# HandheldCon.net
KiCad netlist of a schematic drawn in Altium Designer
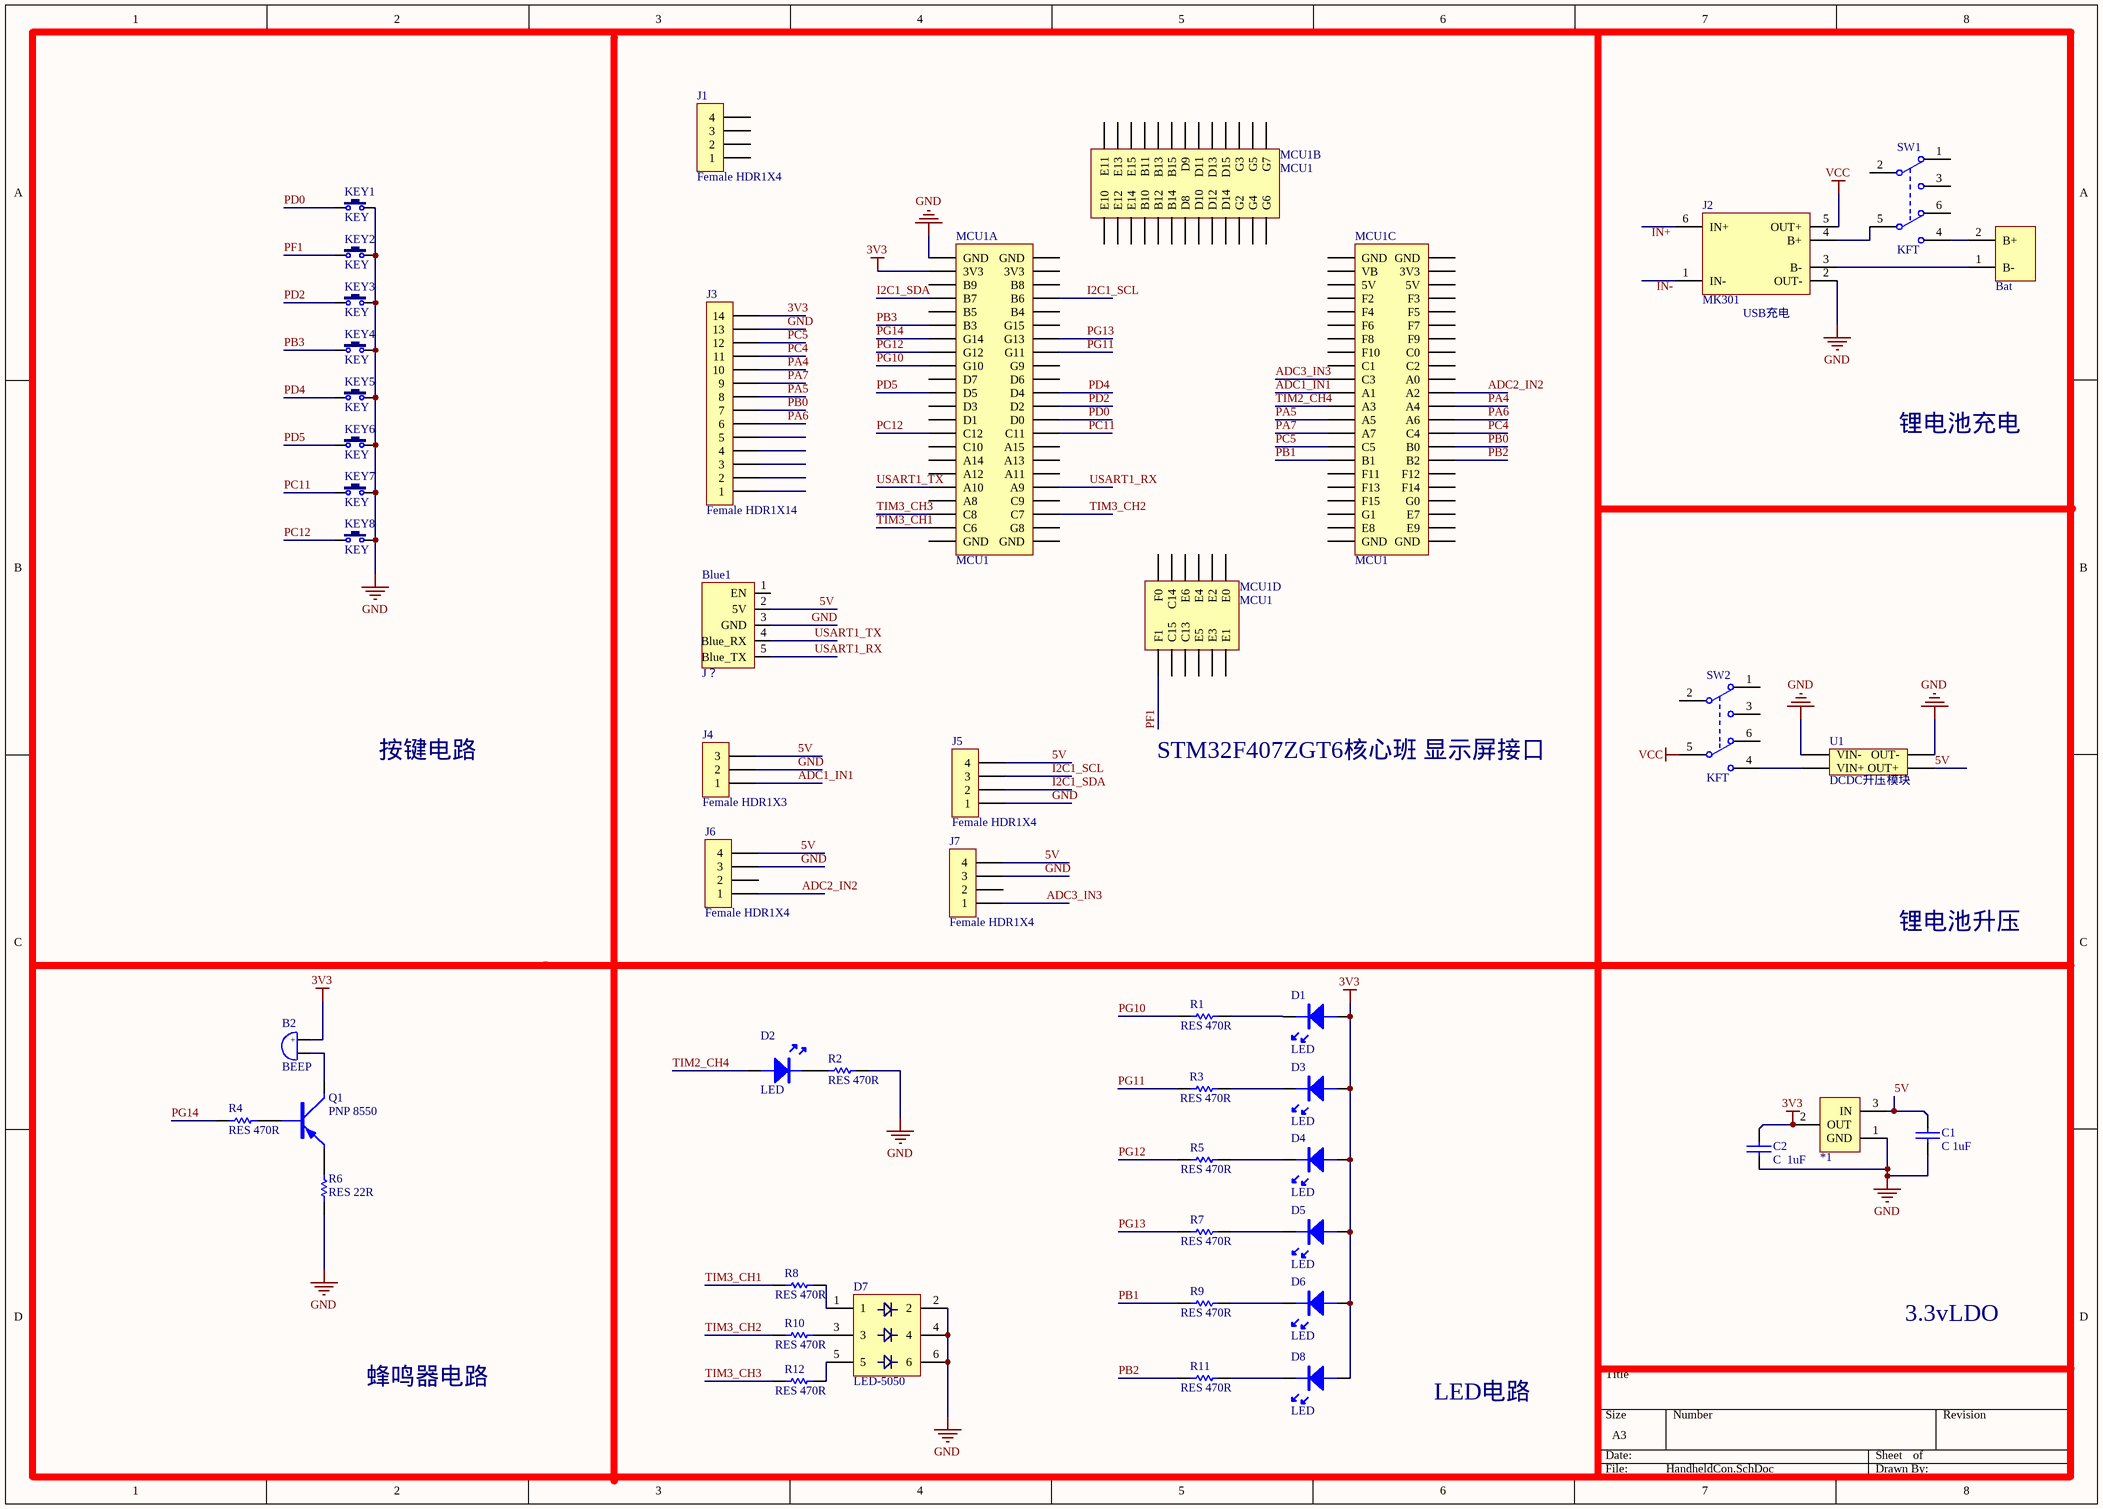
[diagram p0: HandheldCon.SchDoc]

(export (version "E")
  (design (tool "Eeschema 10.0.6"))
  (components
    (comp (ref "*1") (value "3Vout") (footprint "ASM1117_3.3V") (libsource (lib "Schlib1") (part "LM1117")))
    (comp (ref "B1") (value "Bat") (footprint "XH2.54-LI-2P") (libsource (lib "Schlib1") (part "Bettry")))
    (comp (ref "B2")
      (value "BEEP")
      (footprint "BEEP 5x9x5.5")
      (description "蜂鸣器")
      (libsource (lib "蜂鸣器") (part "BEEP"))
    )
    (comp (ref "Blue1")
      (value "J？")
      (footprint "HDR2.54-M-LI-5P")
      (libsource (lib "Schlib_autocar") (part "BlueTooth_net"))
    )
    (comp (ref "C1")
      (value "C 1uF")
      (footprint "1206C")
      (description "Capacitor")
      (libsource (lib "Schlib1") (part "CAP1206"))
    )
    (comp (ref "C2")
      (value "C  1uF")
      (footprint "1206C")
      (description "Capacitor")
      (libsource (lib "Schlib1") (part "CAP1206"))
    )
    (comp (ref "D1") (value "LED") (footprint "LED-0805R") (libsource (lib "LED") (part "LED")))
    (comp (ref "D2") (value "LED") (footprint "LED-0805R") (libsource (lib "LED") (part "LED")))
    (comp (ref "D3") (value "LED") (footprint "LED-0805Y") (libsource (lib "LED") (part "LED")))
    (comp (ref "D4") (value "LED") (footprint "LED-0805B") (libsource (lib "LED") (part "LED")))
    (comp (ref "D5") (value "LED") (footprint "LED-0805G") (libsource (lib "LED") (part "LED")))
    (comp (ref "D6") (value "LED") (footprint "LED-0805G") (libsource (lib "LED") (part "LED")))
    (comp (ref "D7") (value "LED-5050") (footprint "LED-5050W") (libsource (lib "LED") (part "LED-5050")))
    (comp (ref "D8") (value "LED") (footprint "LED-0805G") (libsource (lib "LED") (part "LED")))
    (comp (ref "J1")
      (value "Female HDR1X4")
      (footprint "Fe-HDR1X4/2.54-S")
      (libsource (lib "排母") (part "Female HDR1X4"))
    )
    (comp (ref "J2") (value "MK301") (footprint "TP4056") (libsource (lib "Schlib1") (part "MK301")))
    (comp (ref "J3")
      (value "Female HDR1X14")
      (footprint "Fe-HDR1X14/2.54-S")
      (libsource (lib "排母") (part "Female HDR1X14"))
    )
    (comp (ref "J4")
      (value "Female HDR1X3")
      (footprint "Fe-HDR1X3/2.54-S")
      (libsource (lib "排母") (part "Female HDR1X3"))
    )
    (comp (ref "J5")
      (value "Female HDR1X4")
      (footprint "Fe-HDR1X4/2.54-S")
      (libsource (lib "排母") (part "Female HDR1X4"))
    )
    (comp (ref "J6")
      (value "Female HDR1X4")
      (footprint "Fe-HDR1X4/2.54-S")
      (libsource (lib "排母") (part "Female HDR1X4"))
    )
    (comp (ref "J7")
      (value "Female HDR1X4")
      (footprint "Fe-HDR1X4/2.54-S")
      (libsource (lib "排母") (part "Female HDR1X4"))
    )
    (comp (ref "KEY1")
      (value "KEY")
      (footprint "TSW SMD-6*6*8")
      (description "Tact Switch")
      (libsource (lib "集成库文件") (part "TSW_6X6-SMT"))
    )
    (comp (ref "KEY2")
      (value "KEY")
      (footprint "TSW SMD-6*6*8")
      (description "Tact Switch")
      (libsource (lib "集成库文件") (part "TSW_6X6-SMT"))
    )
    (comp (ref "KEY3")
      (value "KEY")
      (footprint "TSW SMD-6*6*8")
      (description "Tact Switch")
      (libsource (lib "集成库文件") (part "TSW_6X6-SMT"))
    )
    (comp (ref "KEY4")
      (value "KEY")
      (footprint "TSW SMD-6*6*8")
      (description "Tact Switch")
      (libsource (lib "集成库文件") (part "TSW_6X6-SMT"))
    )
    (comp (ref "KEY5")
      (value "KEY")
      (footprint "TSW SMD-6*6*8")
      (description "Tact Switch")
      (libsource (lib "集成库文件") (part "TSW_6X6-SMT"))
    )
    (comp (ref "KEY6")
      (value "KEY")
      (footprint "TSW SMD-6*6*8")
      (description "Tact Switch")
      (libsource (lib "集成库文件") (part "TSW_6X6-SMT"))
    )
    (comp (ref "KEY7")
      (value "KEY")
      (footprint "TSW SMD-6*6*8")
      (description "Tact Switch")
      (libsource (lib "集成库文件") (part "TSW_6X6-SMT"))
    )
    (comp (ref "KEY8")
      (value "KEY")
      (footprint "TSW SMD-6*6*8")
      (description "Tact Switch")
      (libsource (lib "集成库文件") (part "TSW_6X6-SMT"))
    )
    (comp (ref "MCU1") (value "MCU1") (footprint "核心板底座") (libsource (lib "Schlib_autocar") (part "核心板插座")))
    (comp (ref "Q1")
      (value "PNP 8550")
      (footprint "SOT-23")
      (description "PNP三极管")
      (libsource (lib "三极管") (part "PNP"))
    )
    (comp (ref "R1") (value "RES 470R") (footprint "0805R") (libsource (lib "电阻") (part "RES")))
    (comp (ref "R2") (value "RES 470R") (footprint "0805R") (libsource (lib "电阻") (part "RES")))
    (comp (ref "R3") (value "RES 470R") (footprint "0805R") (libsource (lib "电阻") (part "RES")))
    (comp (ref "R4") (value "RES 470R") (footprint "0805R") (libsource (lib "电阻") (part "RES")))
    (comp (ref "R5") (value "RES 470R") (footprint "0805R") (libsource (lib "电阻") (part "RES")))
    (comp (ref "R6") (value "RES 22R") (footprint "0805R") (libsource (lib "电阻") (part "RES")))
    (comp (ref "R7") (value "RES 470R") (footprint "0805R") (libsource (lib "电阻") (part "RES")))
    (comp (ref "R8") (value "RES 470R") (footprint "0805R") (libsource (lib "电阻") (part "RES")))
    (comp (ref "R9") (value "RES 470R") (footprint "0805R") (libsource (lib "电阻") (part "RES")))
    (comp (ref "R10") (value "RES 470R") (footprint "0805R") (libsource (lib "电阻") (part "RES")))
    (comp (ref "R11") (value "RES 470R") (footprint "0805R") (libsource (lib "电阻") (part "RES")))
    (comp (ref "R12") (value "RES 470R") (footprint "0805R") (libsource (lib "电阻") (part "RES")))
    (comp (ref "SW1")
      (value "KFT")
      (footprint "KFT DIP-7X7")
      (description "Self-locking Switch")
      (libsource (lib "Schlib1") (part "KFT_7X7-DIP"))
    )
    (comp (ref "SW2")
      (value "KFT")
      (footprint "KFT DIP-7X7")
      (description "Self-locking Switch")
      (libsource (lib "Schlib1") (part "KFT_7X7-DIP"))
    )
    (comp (ref "U1") (value "DCDC升压模块") (footprint "DCDC升压5V") (libsource (lib "Schlib1") (part "DCDC升压模块")))
  )
  (nets
    (net (code "1") (name "/5V") (class "Default")
      (node (ref "*1") (pin "3") (pinfunction "IN_3") (pintype "power_in"))
      (node (ref "Blue1") (pin "2") (pinfunction "5V_2") (pintype "power_in"))
      (node (ref "C1") (pin "1") (pinfunction "1_1") (pintype "passive"))
      (node (ref "J4") (pin "3") (pinfunction "3_3") (pintype "passive"))
      (node (ref "J5") (pin "4") (pinfunction "4_4") (pintype "passive"))
      (node (ref "J6") (pin "4") (pinfunction "4_4") (pintype "passive"))
      (node (ref "J7") (pin "4") (pinfunction "4_4") (pintype "passive"))
      (node (ref "U1") (pin "1") (pinfunction "OUT+_1") (pintype "passive"))
    )
    (net (code "2") (name "/ADC1_IN1") (class "Default")
      (node (ref "J4") (pin "1") (pinfunction "1_1") (pintype "passive"))
      (node (ref "MCU1") (pin "94") (pinfunction "A1_94") (pintype "passive"))
    )
    (net (code "3") (name "/ADC2_IN2") (class "Default")
      (node (ref "J6") (pin "1") (pinfunction "1_1") (pintype "passive"))
      (node (ref "MCU1") (pin "93") (pinfunction "A2_93") (pintype "passive"))
    )
    (net (code "4") (name "/ADC3_IN3") (class "Default")
      (node (ref "J7") (pin "1") (pinfunction "1_1") (pintype "passive"))
      (node (ref "MCU1") (pin "96") (pinfunction "C3_96") (pintype "passive"))
    )
    (net (code "5") (name "/I2C1_SCL") (class "Default")
      (node (ref "J5") (pin "3") (pinfunction "3_3") (pintype "passive"))
      (node (ref "MCU1") (pin "8") (pinfunction "B6_8") (pintype "passive"))
    )
    (net (code "6") (name "/I2C1_SDA") (class "Default")
      (node (ref "J5") (pin "2") (pinfunction "2_2") (pintype "passive"))
      (node (ref "MCU1") (pin "7") (pinfunction "B7_7") (pintype "passive"))
    )
    (net (code "9") (name "/PA4") (class "Default")
      (node (ref "J3") (pin "10") (pinfunction "10_10") (pintype "passive"))
      (node (ref "MCU1") (pin "91") (pinfunction "A4_91") (pintype "passive"))
    )
    (net (code "10") (name "/PA5") (class "Default")
      (node (ref "J3") (pin "8") (pinfunction "8_8") (pintype "passive"))
      (node (ref "MCU1") (pin "90") (pinfunction "A5_90") (pintype "passive"))
    )
    (net (code "11") (name "/PA6") (class "Default")
      (node (ref "J3") (pin "6") (pinfunction "6_6") (pintype "passive"))
      (node (ref "MCU1") (pin "89") (pinfunction "A6_89") (pintype "passive"))
    )
    (net (code "12") (name "/PA7") (class "Default")
      (node (ref "J3") (pin "9") (pinfunction "9_9") (pintype "passive"))
      (node (ref "MCU1") (pin "88") (pinfunction "A7_88") (pintype "passive"))
    )
    (net (code "13") (name "/PB0") (class "Default")
      (node (ref "J3") (pin "7") (pinfunction "7_7") (pintype "passive"))
      (node (ref "MCU1") (pin "85") (pinfunction "B0_85") (pintype "passive"))
    )
    (net (code "14") (name "/PB1") (class "Default")
      (node (ref "MCU1") (pin "84") (pinfunction "B1_84") (pintype "passive"))
      (node (ref "R9") (pin "1") (pinfunction "1_1") (pintype "passive"))
    )
    (net (code "15") (name "/PB2") (class "Default")
      (node (ref "MCU1") (pin "83") (pinfunction "B2_83") (pintype "passive"))
      (node (ref "R11") (pin "1") (pinfunction "1_1") (pintype "passive"))
    )
    (net (code "16") (name "/PB3") (class "Default")
      (node (ref "KEY4") (pin "1") (pinfunction "1_1") (pintype "passive"))
      (node (ref "MCU1") (pin "11") (pinfunction "B3_11") (pintype "passive"))
    )
    (net (code "17") (name "/PC4") (class "Default")
      (node (ref "J3") (pin "11") (pinfunction "11_11") (pintype "passive"))
      (node (ref "MCU1") (pin "87") (pinfunction "C4_87") (pintype "passive"))
    )
    (net (code "18") (name "/PC5") (class "Default")
      (node (ref "J3") (pin "12") (pinfunction "12_12") (pintype "passive"))
      (node (ref "MCU1") (pin "86") (pinfunction "C5_86") (pintype "passive"))
    )
    (net (code "19") (name "/PC11") (class "Default")
      (node (ref "KEY7") (pin "1") (pinfunction "1_1") (pintype "passive"))
      (node (ref "MCU1") (pin "28") (pinfunction "C11_28") (pintype "passive"))
    )
    (net (code "20") (name "/PC12") (class "Default")
      (node (ref "KEY8") (pin "1") (pinfunction "1_1") (pintype "passive"))
      (node (ref "MCU1") (pin "27") (pinfunction "C12_27") (pintype "passive"))
    )
    (net (code "21") (name "/PD0") (class "Default")
      (node (ref "KEY1") (pin "1") (pinfunction "1_1") (pintype "passive"))
      (node (ref "MCU1") (pin "26") (pinfunction "D0_26") (pintype "passive"))
    )
    (net (code "22") (name "/PD2") (class "Default")
      (node (ref "KEY3") (pin "1") (pinfunction "1_1") (pintype "passive"))
      (node (ref "MCU1") (pin "24") (pinfunction "D2_24") (pintype "passive"))
    )
    (net (code "23") (name "/PD4") (class "Default")
      (node (ref "KEY5") (pin "1") (pinfunction "1_1") (pintype "passive"))
      (node (ref "MCU1") (pin "22") (pinfunction "D4_22") (pintype "passive"))
    )
    (net (code "24") (name "/PD5") (class "Default")
      (node (ref "KEY6") (pin "1") (pinfunction "1_1") (pintype "passive"))
      (node (ref "MCU1") (pin "21") (pinfunction "D5_21") (pintype "passive"))
    )
    (net (code "25") (name "/PF1") (class "Default")
      (node (ref "KEY2") (pin "1") (pinfunction "1_1") (pintype "passive"))
      (node (ref "MCU1") (pin "115") (pinfunction "F1_115") (pintype "passive"))
    )
    (net (code "26") (name "/PG10") (class "Default")
      (node (ref "MCU1") (pin "17") (pinfunction "G10_17") (pintype "passive"))
      (node (ref "R1") (pin "1") (pinfunction "1_1") (pintype "passive"))
    )
    (net (code "27") (name "/PG11") (class "Default")
      (node (ref "MCU1") (pin "16") (pinfunction "G11_16") (pintype "passive"))
      (node (ref "R3") (pin "1") (pinfunction "1_1") (pintype "passive"))
    )
    (net (code "28") (name "/PG12") (class "Default")
      (node (ref "MCU1") (pin "15") (pinfunction "G12_15") (pintype "passive"))
      (node (ref "R5") (pin "1") (pinfunction "1_1") (pintype "passive"))
    )
    (net (code "29") (name "/PG13") (class "Default")
      (node (ref "MCU1") (pin "14") (pinfunction "G13_14") (pintype "passive"))
      (node (ref "R7") (pin "1") (pinfunction "1_1") (pintype "passive"))
    )
    (net (code "30") (name "/PG14") (class "Default")
      (node (ref "MCU1") (pin "13") (pinfunction "G14_13") (pintype "passive"))
      (node (ref "R4") (pin "2") (pinfunction "2_2") (pintype "passive"))
    )
    (net (code "31") (name "/TIM2_CH4") (class "Default")
      (node (ref "D2") (pin "A") (pinfunction "A_A") (pintype "passive"))
      (node (ref "MCU1") (pin "92") (pinfunction "A3_92") (pintype "passive"))
    )
    (net (code "32") (name "/TIM3_CH1") (class "Default")
      (node (ref "MCU1") (pin "41") (pinfunction "C6_41") (pintype "passive"))
      (node (ref "R8") (pin "1") (pinfunction "1_1") (pintype "passive"))
    )
    (net (code "33") (name "/TIM3_CH2") (class "Default")
      (node (ref "MCU1") (pin "40") (pinfunction "C7_40") (pintype "passive"))
      (node (ref "R10") (pin "1") (pinfunction "1_1") (pintype "passive"))
    )
    (net (code "34") (name "/TIM3_CH3") (class "Default")
      (node (ref "MCU1") (pin "39") (pinfunction "C8_39") (pintype "passive"))
      (node (ref "R12") (pin "1") (pinfunction "1_1") (pintype "passive"))
    )
    (net (code "35") (name "/USART1_RX") (class "Default")
      (node (ref "Blue1") (pin "5") (pinfunction "Blue_TX_5") (pintype "passive"))
      (node (ref "MCU1") (pin "36") (pinfunction "A9_36") (pintype "passive"))
    )
    (net (code "36") (name "/USART1_TX") (class "Default")
      (node (ref "Blue1") (pin "4") (pinfunction "Blue_RX_4") (pintype "passive"))
      (node (ref "MCU1") (pin "35") (pinfunction "A10_35") (pintype "passive"))
    )
    (net (code "37") (name "3V3") (class "Default")
      (node (ref "*1") (pin "2") (pinfunction "OUT_2") (pintype "power_in"))
      (node (ref "B2") (pin "1") (pinfunction "1_1") (pintype "passive"))
      (node (ref "C2") (pin "1") (pinfunction "1_1") (pintype "passive"))
      (node (ref "D1") (pin "A") (pinfunction "A_A") (pintype "passive"))
      (node (ref "D3") (pin "A") (pinfunction "A_A") (pintype "passive"))
      (node (ref "D4") (pin "A") (pinfunction "A_A") (pintype "passive"))
      (node (ref "D5") (pin "A") (pinfunction "A_A") (pintype "passive"))
      (node (ref "D6") (pin "A") (pinfunction "A_A") (pintype "passive"))
      (node (ref "D8") (pin "A") (pinfunction "A_A") (pintype "passive"))
      (node (ref "J3") (pin "14") (pinfunction "14_14") (pintype "passive"))
      (node (ref "MCU1") (pin "3") (pinfunction "3V3_3") (pintype "passive"))
    )
    (net (code "38") (name "GND") (class "Default")
      (node (ref "*1") (pin "1") (pinfunction "GND_1") (pintype "power_in"))
      (node (ref "Blue1") (pin "3") (pinfunction "GND_3") (pintype "power_in"))
      (node (ref "C1") (pin "2") (pinfunction "2_2") (pintype "passive"))
      (node (ref "C2") (pin "2") (pinfunction "2_2") (pintype "passive"))
      (node (ref "D7") (pin "2") (pinfunction "2_2") (pintype "passive"))
      (node (ref "D7") (pin "4") (pinfunction "4_4") (pintype "passive"))
      (node (ref "D7") (pin "6") (pinfunction "6_6") (pintype "passive"))
      (node (ref "J2") (pin "2") (pinfunction "OUT-_2") (pintype "power_in"))
      (node (ref "J3") (pin "13") (pinfunction "13_13") (pintype "passive"))
      (node (ref "J4") (pin "2") (pinfunction "2_2") (pintype "passive"))
      (node (ref "J5") (pin "1") (pinfunction "1_1") (pintype "passive"))
      (node (ref "J6") (pin "3") (pinfunction "3_3") (pintype "passive"))
      (node (ref "J7") (pin "3") (pinfunction "3_3") (pintype "passive"))
      (node (ref "KEY1") (pin "2") (pinfunction "2_2") (pintype "passive"))
      (node (ref "KEY2") (pin "2") (pinfunction "2_2") (pintype "passive"))
      (node (ref "KEY3") (pin "2") (pinfunction "2_2") (pintype "passive"))
      (node (ref "KEY4") (pin "2") (pinfunction "2_2") (pintype "passive"))
      (node (ref "KEY5") (pin "2") (pinfunction "2_2") (pintype "passive"))
      (node (ref "KEY6") (pin "2") (pinfunction "2_2") (pintype "passive"))
      (node (ref "KEY7") (pin "2") (pinfunction "2_2") (pintype "passive"))
      (node (ref "KEY8") (pin "2") (pinfunction "2_2") (pintype "passive"))
      (node (ref "MCU1") (pin "1") (pinfunction "GND_1") (pintype "power_in"))
      (node (ref "R2") (pin "1") (pinfunction "1_1") (pintype "passive"))
      (node (ref "R6") (pin "2") (pinfunction "2_2") (pintype "passive"))
      (node (ref "U1") (pin "2") (pinfunction "OUT-_2") (pintype "passive"))
      (node (ref "U1") (pin "3") (pinfunction "VIN-_3") (pintype "passive"))
    )
    (net (code "39") (name "Net-(B1-B+)") (class "Default")
      (node (ref "B1") (pin "2") (pinfunction "B+_2") (pintype "power_in"))
      (node (ref "SW1") (pin "4") (pinfunction "NO2_4") (pintype "passive"))
    )
    (net (code "40") (name "Net-(B1-B-)") (class "Default")
      (node (ref "B1") (pin "1") (pinfunction "B-_1") (pintype "power_in"))
      (node (ref "J2") (pin "3") (pinfunction "B-_3") (pintype "power_in"))
    )
    (net (code "41") (name "Net-(B2-Pad2)") (class "Default")
      (node (ref "B2") (pin "2") (pinfunction "2_2") (pintype "passive"))
      (node (ref "Q1") (pin "C") (pinfunction "C_C") (pintype "passive"))
    )
    (net (code "42") (name "Net-(D1-PadK)") (class "Default")
      (node (ref "D1") (pin "K") (pinfunction "K_K") (pintype "passive"))
      (node (ref "R1") (pin "2") (pinfunction "2_2") (pintype "passive"))
    )
    (net (code "43") (name "Net-(D2-PadK)") (class "Default")
      (node (ref "D2") (pin "K") (pinfunction "K_K") (pintype "passive"))
      (node (ref "R2") (pin "2") (pinfunction "2_2") (pintype "passive"))
    )
    (net (code "44") (name "Net-(D3-PadK)") (class "Default")
      (node (ref "D3") (pin "K") (pinfunction "K_K") (pintype "passive"))
      (node (ref "R3") (pin "2") (pinfunction "2_2") (pintype "passive"))
    )
    (net (code "45") (name "Net-(D4-PadK)") (class "Default")
      (node (ref "D4") (pin "K") (pinfunction "K_K") (pintype "passive"))
      (node (ref "R5") (pin "2") (pinfunction "2_2") (pintype "passive"))
    )
    (net (code "46") (name "Net-(D5-PadK)") (class "Default")
      (node (ref "D5") (pin "K") (pinfunction "K_K") (pintype "passive"))
      (node (ref "R7") (pin "2") (pinfunction "2_2") (pintype "passive"))
    )
    (net (code "47") (name "Net-(D6-PadK)") (class "Default")
      (node (ref "D6") (pin "K") (pinfunction "K_K") (pintype "passive"))
      (node (ref "R9") (pin "2") (pinfunction "2_2") (pintype "passive"))
    )
    (net (code "48") (name "Net-(D7-Pad1)") (class "Default")
      (node (ref "D7") (pin "1") (pinfunction "1_1") (pintype "passive"))
      (node (ref "R8") (pin "2") (pinfunction "2_2") (pintype "passive"))
    )
    (net (code "49") (name "Net-(D7-Pad3)") (class "Default")
      (node (ref "D7") (pin "3") (pinfunction "3_3") (pintype "passive"))
      (node (ref "R10") (pin "2") (pinfunction "2_2") (pintype "passive"))
    )
    (net (code "50") (name "Net-(D7-Pad5)") (class "Default")
      (node (ref "D7") (pin "5") (pinfunction "5_5") (pintype "passive"))
      (node (ref "R12") (pin "2") (pinfunction "2_2") (pintype "passive"))
    )
    (net (code "51") (name "Net-(D8-PadK)") (class "Default")
      (node (ref "D8") (pin "K") (pinfunction "K_K") (pintype "passive"))
      (node (ref "R11") (pin "2") (pinfunction "2_2") (pintype "passive"))
    )
    (net (code "52") (name "Net-(J2-B+)") (class "Default")
      (node (ref "J2") (pin "4") (pinfunction "B+_4") (pintype "power_in"))
      (node (ref "SW1") (pin "5") (pinfunction "COM2_5") (pintype "passive"))
    )
    (net (code "53") (name "Net-(Q1-PadB)") (class "Default")
      (node (ref "Q1") (pin "B") (pinfunction "B_B") (pintype "passive"))
      (node (ref "R4") (pin "1") (pinfunction "1_1") (pintype "passive"))
    )
    (net (code "54") (name "Net-(Q1-PadE)") (class "Default")
      (node (ref "Q1") (pin "E") (pinfunction "E_E") (pintype "passive"))
      (node (ref "R6") (pin "1") (pinfunction "1_1") (pintype "passive"))
    )
    (net (code "55") (name "Net-(SW2-NO2)") (class "Default")
      (node (ref "SW2") (pin "4") (pinfunction "NO2_4") (pintype "passive"))
      (node (ref "U1") (pin "4") (pinfunction "VIN+_4") (pintype "passive"))
    )
    (net (code "56") (name "VCC") (class "Default")
      (node (ref "J2") (pin "5") (pinfunction "OUT+_5") (pintype "power_in"))
      (node (ref "SW2") (pin "5") (pinfunction "COM2_5") (pintype "passive"))
    )
    (net (code "57") (name "unconnected-(Blue1-EN-Pad1)") (class "Default")
      (node (ref "Blue1") (pin "1") (pinfunction "EN_1") (pintype "passive"))
    )
    (net (code "58") (name "unconnected-(J1-Pad1)") (class "Default")
      (node (ref "J1") (pin "1") (pinfunction "1_1") (pintype "passive"))
    )
    (net (code "59") (name "unconnected-(J1-Pad2)") (class "Default")
      (node (ref "J1") (pin "2") (pinfunction "2_2") (pintype "passive"))
    )
    (net (code "60") (name "unconnected-(J1-Pad3)") (class "Default")
      (node (ref "J1") (pin "3") (pinfunction "3_3") (pintype "passive"))
    )
    (net (code "61") (name "unconnected-(J1-Pad4)") (class "Default")
      (node (ref "J1") (pin "4") (pinfunction "4_4") (pintype "passive"))
    )
    (net (code "62") (name "unconnected-(J2-IN+-Pad6)") (class "Default")
      (node (ref "J2") (pin "6") (pinfunction "IN+_6") (pintype "power_in"))
    )
    (net (code "63") (name "unconnected-(J2-IN--Pad1)") (class "Default")
      (node (ref "J2") (pin "1") (pinfunction "IN-_1") (pintype "power_in"))
    )
    (net (code "64") (name "unconnected-(J3-Pad1)") (class "Default")
      (node (ref "J3") (pin "1") (pinfunction "1_1") (pintype "passive"))
    )
    (net (code "65") (name "unconnected-(J3-Pad2)") (class "Default")
      (node (ref "J3") (pin "2") (pinfunction "2_2") (pintype "passive"))
    )
    (net (code "66") (name "unconnected-(J3-Pad3)") (class "Default")
      (node (ref "J3") (pin "3") (pinfunction "3_3") (pintype "passive"))
    )
    (net (code "67") (name "unconnected-(J3-Pad4)") (class "Default")
      (node (ref "J3") (pin "4") (pinfunction "4_4") (pintype "passive"))
    )
    (net (code "68") (name "unconnected-(J3-Pad5)") (class "Default")
      (node (ref "J3") (pin "5") (pinfunction "5_5") (pintype "passive"))
    )
    (net (code "69") (name "unconnected-(J6-Pad2)") (class "Default")
      (node (ref "J6") (pin "2") (pinfunction "2_2") (pintype "passive"))
    )
    (net (code "70") (name "unconnected-(J7-Pad2)") (class "Default")
      (node (ref "J7") (pin "2") (pinfunction "2_2") (pintype "passive"))
    )
    (net (code "71") (name "unconnected-(MCU1A-3V3-Pad4)") (class "Default")
      (node (ref "MCU1") (pin "4") (pinfunction "3V3_4") (pintype "passive"))
    )
    (net (code "72") (name "unconnected-(MCU1A-A8-Pad37)") (class "Default")
      (node (ref "MCU1") (pin "37") (pinfunction "A8_37") (pintype "passive"))
    )
    (net (code "73") (name "unconnected-(MCU1A-A11-Pad34)") (class "Default")
      (node (ref "MCU1") (pin "34") (pinfunction "A11_34") (pintype "passive"))
    )
    (net (code "74") (name "unconnected-(MCU1A-A12-Pad33)") (class "Default")
      (node (ref "MCU1") (pin "33") (pinfunction "A12_33") (pintype "passive"))
    )
    (net (code "75") (name "unconnected-(MCU1A-A13-Pad32)") (class "Default")
      (node (ref "MCU1") (pin "32") (pinfunction "A13_32") (pintype "passive"))
    )
    (net (code "76") (name "unconnected-(MCU1A-A14-Pad31)") (class "Default")
      (node (ref "MCU1") (pin "31") (pinfunction "A14_31") (pintype "passive"))
    )
    (net (code "77") (name "unconnected-(MCU1A-A15-Pad30)") (class "Default")
      (node (ref "MCU1") (pin "30") (pinfunction "A15_30") (pintype "passive"))
    )
    (net (code "78") (name "unconnected-(MCU1A-B4-Pad10)") (class "Default")
      (node (ref "MCU1") (pin "10") (pinfunction "B4_10") (pintype "passive"))
    )
    (net (code "79") (name "unconnected-(MCU1A-B5-Pad9)") (class "Default")
      (node (ref "MCU1") (pin "9") (pinfunction "B5_9") (pintype "passive"))
    )
    (net (code "80") (name "unconnected-(MCU1A-B8-Pad6)") (class "Default")
      (node (ref "MCU1") (pin "6") (pinfunction "B8_6") (pintype "passive"))
    )
    (net (code "81") (name "unconnected-(MCU1A-B9-Pad5)") (class "Default")
      (node (ref "MCU1") (pin "5") (pinfunction "B9_5") (pintype "passive"))
    )
    (net (code "82") (name "unconnected-(MCU1A-C9-Pad38)") (class "Default")
      (node (ref "MCU1") (pin "38") (pinfunction "C9_38") (pintype "passive"))
    )
    (net (code "83") (name "unconnected-(MCU1A-C10-Pad29)") (class "Default")
      (node (ref "MCU1") (pin "29") (pinfunction "C10_29") (pintype "passive"))
    )
    (net (code "84") (name "unconnected-(MCU1A-D1-Pad25)") (class "Default")
      (node (ref "MCU1") (pin "25") (pinfunction "D1_25") (pintype "passive"))
    )
    (net (code "85") (name "unconnected-(MCU1A-D3-Pad23)") (class "Default")
      (node (ref "MCU1") (pin "23") (pinfunction "D3_23") (pintype "passive"))
    )
    (net (code "86") (name "unconnected-(MCU1A-D6-Pad20)") (class "Default")
      (node (ref "MCU1") (pin "20") (pinfunction "D6_20") (pintype "passive"))
    )
    (net (code "87") (name "unconnected-(MCU1A-D7-Pad19)") (class "Default")
      (node (ref "MCU1") (pin "19") (pinfunction "D7_19") (pintype "passive"))
    )
    (net (code "88") (name "unconnected-(MCU1A-G8-Pad42)") (class "Default")
      (node (ref "MCU1") (pin "42") (pinfunction "G8_42") (pintype "passive"))
    )
    (net (code "89") (name "unconnected-(MCU1A-G9-Pad18)") (class "Default")
      (node (ref "MCU1") (pin "18") (pinfunction "G9_18") (pintype "passive"))
    )
    (net (code "90") (name "unconnected-(MCU1A-G15-Pad12)") (class "Default")
      (node (ref "MCU1") (pin "12") (pinfunction "G15_12") (pintype "passive"))
    )
    (net (code "91") (name "unconnected-(MCU1A-GND-Pad2)") (class "Default")
      (node (ref "MCU1") (pin "2") (pinfunction "GND_2") (pintype "power_in"))
    )
    (net (code "92") (name "unconnected-(MCU1A-GND-Pad43)") (class "Default")
      (node (ref "MCU1") (pin "43") (pinfunction "GND_43") (pintype "passive"))
    )
    (net (code "93") (name "unconnected-(MCU1A-GND-Pad44)") (class "Default")
      (node (ref "MCU1") (pin "44") (pinfunction "GND_44") (pintype "passive"))
    )
    (net (code "94") (name "unconnected-(MCU1B-B10-Pad64)") (class "Default")
      (node (ref "MCU1") (pin "64") (pinfunction "B10_64") (pintype "passive"))
    )
    (net (code "95") (name "unconnected-(MCU1B-B11-Pad63)") (class "Default")
      (node (ref "MCU1") (pin "63") (pinfunction "B11_63") (pintype "passive"))
    )
    (net (code "96") (name "unconnected-(MCU1B-B12-Pad62)") (class "Default")
      (node (ref "MCU1") (pin "62") (pinfunction "B12_62") (pintype "passive"))
    )
    (net (code "97") (name "unconnected-(MCU1B-B13-Pad61)") (class "Default")
      (node (ref "MCU1") (pin "61") (pinfunction "B13_61") (pintype "passive"))
    )
    (net (code "98") (name "unconnected-(MCU1B-B14-Pad60)") (class "Default")
      (node (ref "MCU1") (pin "60") (pinfunction "B14_60") (pintype "passive"))
    )
    (net (code "99") (name "unconnected-(MCU1B-B15-Pad59)") (class "Default")
      (node (ref "MCU1") (pin "59") (pinfunction "B15_59") (pintype "passive"))
    )
    (net (code "100") (name "unconnected-(MCU1B-D8-Pad58)") (class "Default")
      (node (ref "MCU1") (pin "58") (pinfunction "D8_58") (pintype "passive"))
    )
    (net (code "101") (name "unconnected-(MCU1B-D9-Pad57)") (class "Default")
      (node (ref "MCU1") (pin "57") (pinfunction "D9_57") (pintype "passive"))
    )
    (net (code "102") (name "unconnected-(MCU1B-D10-Pad56)") (class "Default")
      (node (ref "MCU1") (pin "56") (pinfunction "D10_56") (pintype "passive"))
    )
    (net (code "103") (name "unconnected-(MCU1B-D11-Pad55)") (class "Default")
      (node (ref "MCU1") (pin "55") (pinfunction "D11_55") (pintype "passive"))
    )
    (net (code "104") (name "unconnected-(MCU1B-D12-Pad54)") (class "Default")
      (node (ref "MCU1") (pin "54") (pinfunction "D12_54") (pintype "passive"))
    )
    (net (code "105") (name "unconnected-(MCU1B-D13-Pad53)") (class "Default")
      (node (ref "MCU1") (pin "53") (pinfunction "D13_53") (pintype "passive"))
    )
    (net (code "106") (name "unconnected-(MCU1B-D14-Pad52)") (class "Default")
      (node (ref "MCU1") (pin "52") (pinfunction "D14_52") (pintype "passive"))
    )
    (net (code "107") (name "unconnected-(MCU1B-D15-Pad51)") (class "Default")
      (node (ref "MCU1") (pin "51") (pinfunction "D15_51") (pintype "passive"))
    )
    (net (code "108") (name "unconnected-(MCU1B-E10-Pad70)") (class "Default")
      (node (ref "MCU1") (pin "70") (pinfunction "E10_70") (pintype "passive"))
    )
    (net (code "109") (name "unconnected-(MCU1B-E11-Pad69)") (class "Default")
      (node (ref "MCU1") (pin "69") (pinfunction "E11_69") (pintype "passive"))
    )
    (net (code "110") (name "unconnected-(MCU1B-E12-Pad68)") (class "Default")
      (node (ref "MCU1") (pin "68") (pinfunction "E12_68") (pintype "passive"))
    )
    (net (code "111") (name "unconnected-(MCU1B-E13-Pad67)") (class "Default")
      (node (ref "MCU1") (pin "67") (pinfunction "E13_67") (pintype "passive"))
    )
    (net (code "112") (name "unconnected-(MCU1B-E14-Pad66)") (class "Default")
      (node (ref "MCU1") (pin "66") (pinfunction "E14_66") (pintype "passive"))
    )
    (net (code "113") (name "unconnected-(MCU1B-E15-Pad65)") (class "Default")
      (node (ref "MCU1") (pin "65") (pinfunction "E15_65") (pintype "passive"))
    )
    (net (code "114") (name "unconnected-(MCU1B-G2-Pad50)") (class "Default")
      (node (ref "MCU1") (pin "50") (pinfunction "G2_50") (pintype "passive"))
    )
    (net (code "115") (name "unconnected-(MCU1B-G3-Pad49)") (class "Default")
      (node (ref "MCU1") (pin "49") (pinfunction "G3_49") (pintype "passive"))
    )
    (net (code "116") (name "unconnected-(MCU1B-G4-Pad48)") (class "Default")
      (node (ref "MCU1") (pin "48") (pinfunction "G4_48") (pintype "passive"))
    )
    (net (code "117") (name "unconnected-(MCU1B-G5-Pad47)") (class "Default")
      (node (ref "MCU1") (pin "47") (pinfunction "G5_47") (pintype "passive"))
    )
    (net (code "118") (name "unconnected-(MCU1B-G6-Pad46)") (class "Default")
      (node (ref "MCU1") (pin "46") (pinfunction "G6_46") (pintype "passive"))
    )
    (net (code "119") (name "unconnected-(MCU1B-G7-Pad45)") (class "Default")
      (node (ref "MCU1") (pin "45") (pinfunction "G7_45") (pintype "passive"))
    )
    (net (code "120") (name "unconnected-(MCU1C-3V3-Pad111)") (class "Default")
      (node (ref "MCU1") (pin "111") (pinfunction "3V3_111") (pintype "passive"))
    )
    (net (code "121") (name "unconnected-(MCU1C-5V-Pad109)") (class "Default")
      (node (ref "MCU1") (pin "109") (pinfunction "5V_109") (pintype "passive"))
    )
    (net (code "122") (name "unconnected-(MCU1C-5V-Pad110)") (class "Default")
      (node (ref "MCU1") (pin "110") (pinfunction "5V_110") (pintype "passive"))
    )
    (net (code "123") (name "unconnected-(MCU1C-A0-Pad95)") (class "Default")
      (node (ref "MCU1") (pin "95") (pinfunction "A0_95") (pintype "passive"))
    )
    (net (code "124") (name "unconnected-(MCU1C-C0-Pad99)") (class "Default")
      (node (ref "MCU1") (pin "99") (pinfunction "C0_99") (pintype "passive"))
    )
    (net (code "125") (name "unconnected-(MCU1C-C1-Pad98)") (class "Default")
      (node (ref "MCU1") (pin "98") (pinfunction "C1_98") (pintype "passive"))
    )
    (net (code "126") (name "unconnected-(MCU1C-C2-Pad97)") (class "Default")
      (node (ref "MCU1") (pin "97") (pinfunction "C2_97") (pintype "passive"))
    )
    (net (code "127") (name "unconnected-(MCU1C-E7-Pad75)") (class "Default")
      (node (ref "MCU1") (pin "75") (pinfunction "E7_75") (pintype "passive"))
    )
    (net (code "128") (name "unconnected-(MCU1C-E8-Pad74)") (class "Default")
      (node (ref "MCU1") (pin "74") (pinfunction "E8_74") (pintype "passive"))
    )
    (net (code "129") (name "unconnected-(MCU1C-E9-Pad73)") (class "Default")
      (node (ref "MCU1") (pin "73") (pinfunction "E9_73") (pintype "passive"))
    )
    (net (code "130") (name "unconnected-(MCU1C-F2-Pad108)") (class "Default")
      (node (ref "MCU1") (pin "108") (pinfunction "F2_108") (pintype "passive"))
    )
    (net (code "131") (name "unconnected-(MCU1C-F3-Pad107)") (class "Default")
      (node (ref "MCU1") (pin "107") (pinfunction "F3_107") (pintype "passive"))
    )
    (net (code "132") (name "unconnected-(MCU1C-F4-Pad106)") (class "Default")
      (node (ref "MCU1") (pin "106") (pinfunction "F4_106") (pintype "passive"))
    )
    (net (code "133") (name "unconnected-(MCU1C-F5-Pad105)") (class "Default")
      (node (ref "MCU1") (pin "105") (pinfunction "F5_105") (pintype "passive"))
    )
    (net (code "134") (name "unconnected-(MCU1C-F6-Pad104)") (class "Default")
      (node (ref "MCU1") (pin "104") (pinfunction "F6_104") (pintype "passive"))
    )
    (net (code "135") (name "unconnected-(MCU1C-F7-Pad103)") (class "Default")
      (node (ref "MCU1") (pin "103") (pinfunction "F7_103") (pintype "passive"))
    )
    (net (code "136") (name "unconnected-(MCU1C-F8-Pad102)") (class "Default")
      (node (ref "MCU1") (pin "102") (pinfunction "F8_102") (pintype "passive"))
    )
    (net (code "137") (name "unconnected-(MCU1C-F9-Pad101)") (class "Default")
      (node (ref "MCU1") (pin "101") (pinfunction "F9_101") (pintype "passive"))
    )
    (net (code "138") (name "unconnected-(MCU1C-F10-Pad100)") (class "Default")
      (node (ref "MCU1") (pin "100") (pinfunction "F10_100") (pintype "passive"))
    )
    (net (code "139") (name "unconnected-(MCU1C-F11-Pad82)") (class "Default")
      (node (ref "MCU1") (pin "82") (pinfunction "F11_82") (pintype "passive"))
    )
    (net (code "140") (name "unconnected-(MCU1C-F12-Pad81)") (class "Default")
      (node (ref "MCU1") (pin "81") (pinfunction "F12_81") (pintype "passive"))
    )
    (net (code "141") (name "unconnected-(MCU1C-F13-Pad80)") (class "Default")
      (node (ref "MCU1") (pin "80") (pinfunction "F13_80") (pintype "passive"))
    )
    (net (code "142") (name "unconnected-(MCU1C-F14-Pad79)") (class "Default")
      (node (ref "MCU1") (pin "79") (pinfunction "F14_79") (pintype "passive"))
    )
    (net (code "143") (name "unconnected-(MCU1C-F15-Pad78)") (class "Default")
      (node (ref "MCU1") (pin "78") (pinfunction "F15_78") (pintype "passive"))
    )
    (net (code "144") (name "unconnected-(MCU1C-G0-Pad77)") (class "Default")
      (node (ref "MCU1") (pin "77") (pinfunction "G0_77") (pintype "passive"))
    )
    (net (code "145") (name "unconnected-(MCU1C-G1-Pad76)") (class "Default")
      (node (ref "MCU1") (pin "76") (pinfunction "G1_76") (pintype "passive"))
    )
    (net (code "146") (name "unconnected-(MCU1C-GND-Pad71)") (class "Default")
      (node (ref "MCU1") (pin "71") (pinfunction "GND_71") (pintype "passive"))
    )
    (net (code "147") (name "unconnected-(MCU1C-GND-Pad72)") (class "Default")
      (node (ref "MCU1") (pin "72") (pinfunction "GND_72") (pintype "passive"))
    )
    (net (code "148") (name "unconnected-(MCU1C-GND-Pad113)") (class "Default")
      (node (ref "MCU1") (pin "113") (pinfunction "GND_113") (pintype "passive"))
    )
    (net (code "149") (name "unconnected-(MCU1C-GND-Pad114)") (class "Default")
      (node (ref "MCU1") (pin "114") (pinfunction "GND_114") (pintype "passive"))
    )
    (net (code "150") (name "unconnected-(MCU1C-VB-Pad112)") (class "Default")
      (node (ref "MCU1") (pin "112") (pinfunction "VB_112") (pintype "passive"))
    )
    (net (code "151") (name "unconnected-(MCU1D-C13-Pad119)") (class "Default")
      (node (ref "MCU1") (pin "119") (pinfunction "C13_119") (pintype "passive"))
    )
    (net (code "152") (name "unconnected-(MCU1D-C14-Pad118)") (class "Default")
      (node (ref "MCU1") (pin "118") (pinfunction "C14_118") (pintype "passive"))
    )
    (net (code "153") (name "unconnected-(MCU1D-C15-Pad117)") (class "Default")
      (node (ref "MCU1") (pin "117") (pinfunction "C15_117") (pintype "passive"))
    )
    (net (code "154") (name "unconnected-(MCU1D-E0-Pad126)") (class "Default")
      (node (ref "MCU1") (pin "126") (pinfunction "E0_126") (pintype "passive"))
    )
    (net (code "155") (name "unconnected-(MCU1D-E1-Pad125)") (class "Default")
      (node (ref "MCU1") (pin "125") (pinfunction "E1_125") (pintype "passive"))
    )
    (net (code "156") (name "unconnected-(MCU1D-E2-Pad124)") (class "Default")
      (node (ref "MCU1") (pin "124") (pinfunction "E2_124") (pintype "passive"))
    )
    (net (code "157") (name "unconnected-(MCU1D-E3-Pad123)") (class "Default")
      (node (ref "MCU1") (pin "123") (pinfunction "E3_123") (pintype "passive"))
    )
    (net (code "158") (name "unconnected-(MCU1D-E4-Pad122)") (class "Default")
      (node (ref "MCU1") (pin "122") (pinfunction "E4_122") (pintype "passive"))
    )
    (net (code "159") (name "unconnected-(MCU1D-E5-Pad121)") (class "Default")
      (node (ref "MCU1") (pin "121") (pinfunction "E5_121") (pintype "passive"))
    )
    (net (code "160") (name "unconnected-(MCU1D-E6-Pad120)") (class "Default")
      (node (ref "MCU1") (pin "120") (pinfunction "E6_120") (pintype "passive"))
    )
    (net (code "161") (name "unconnected-(MCU1D-F0-Pad116)") (class "Default")
      (node (ref "MCU1") (pin "116") (pinfunction "F0_116") (pintype "passive"))
    )
    (net (code "162") (name "unconnected-(SW1-COM2-Pad2)") (class "Default")
      (node (ref "SW1") (pin "2") (pinfunction "COM2_2") (pintype "passive"))
    )
    (net (code "163") (name "unconnected-(SW1-NC1-Pad1)") (class "Default")
      (node (ref "SW1") (pin "1") (pinfunction "NC1_1") (pintype "passive"))
    )
    (net (code "164") (name "unconnected-(SW1-NC2-Pad6)") (class "Default")
      (node (ref "SW1") (pin "6") (pinfunction "NC2_6") (pintype "passive"))
    )
    (net (code "165") (name "unconnected-(SW1-NO1-Pad3)") (class "Default")
      (node (ref "SW1") (pin "3") (pinfunction "NO1_3") (pintype "passive"))
    )
    (net (code "166") (name "unconnected-(SW2-COM2-Pad2)") (class "Default")
      (node (ref "SW2") (pin "2") (pinfunction "COM2_2") (pintype "passive"))
    )
    (net (code "167") (name "unconnected-(SW2-NC1-Pad1)") (class "Default")
      (node (ref "SW2") (pin "1") (pinfunction "NC1_1") (pintype "passive"))
    )
    (net (code "168") (name "unconnected-(SW2-NC2-Pad6)") (class "Default")
      (node (ref "SW2") (pin "6") (pinfunction "NC2_6") (pintype "passive"))
    )
    (net (code "169") (name "unconnected-(SW2-NO1-Pad3)") (class "Default")
      (node (ref "SW2") (pin "3") (pinfunction "NO1_3") (pintype "passive"))
    )
  )
)
